# LitBit.net
KiCad netlist of a schematic drawn in EAGLE
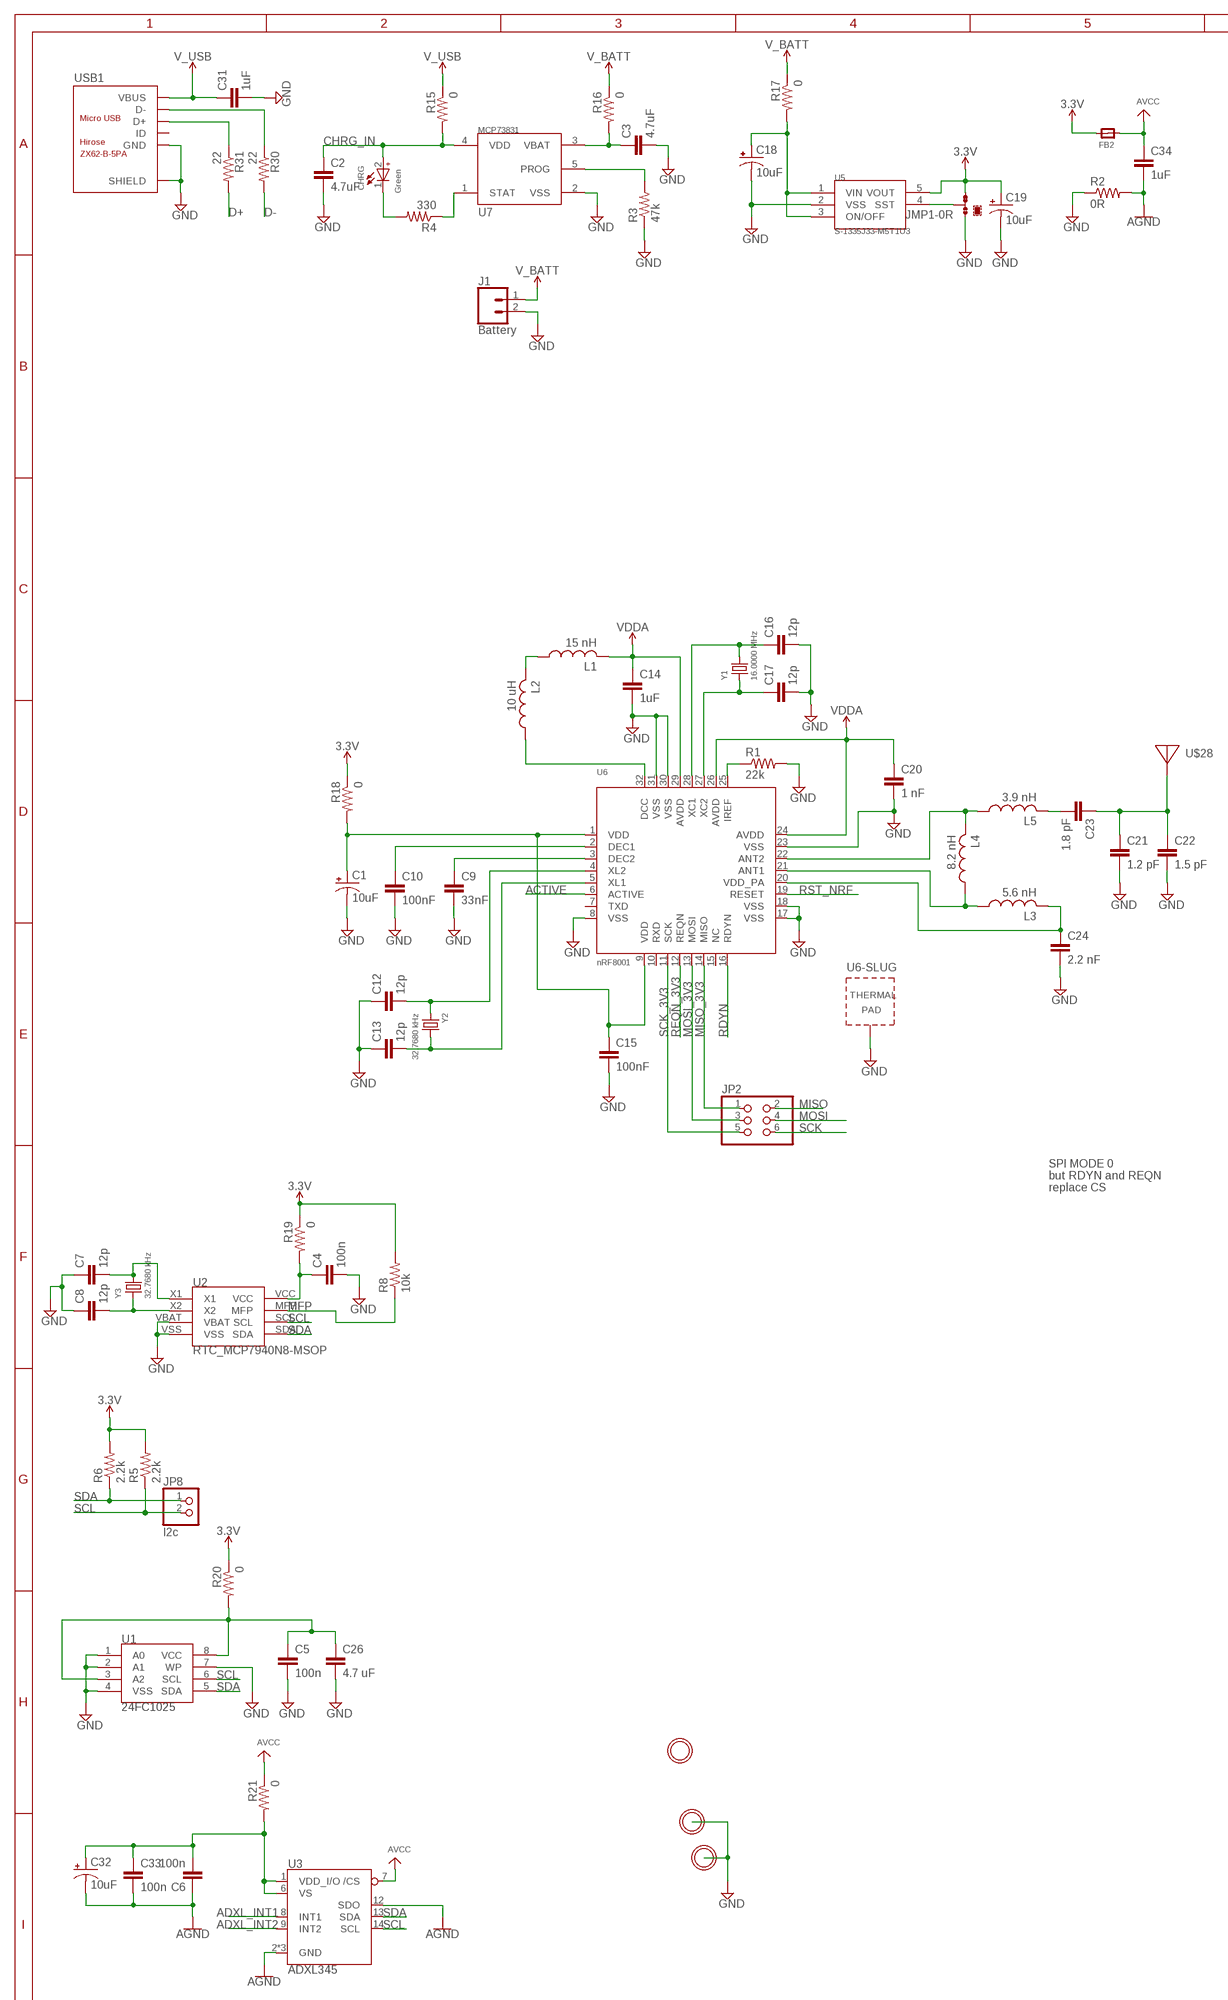
[diagram p0: schematic, sheet 1, part 1 of 2]
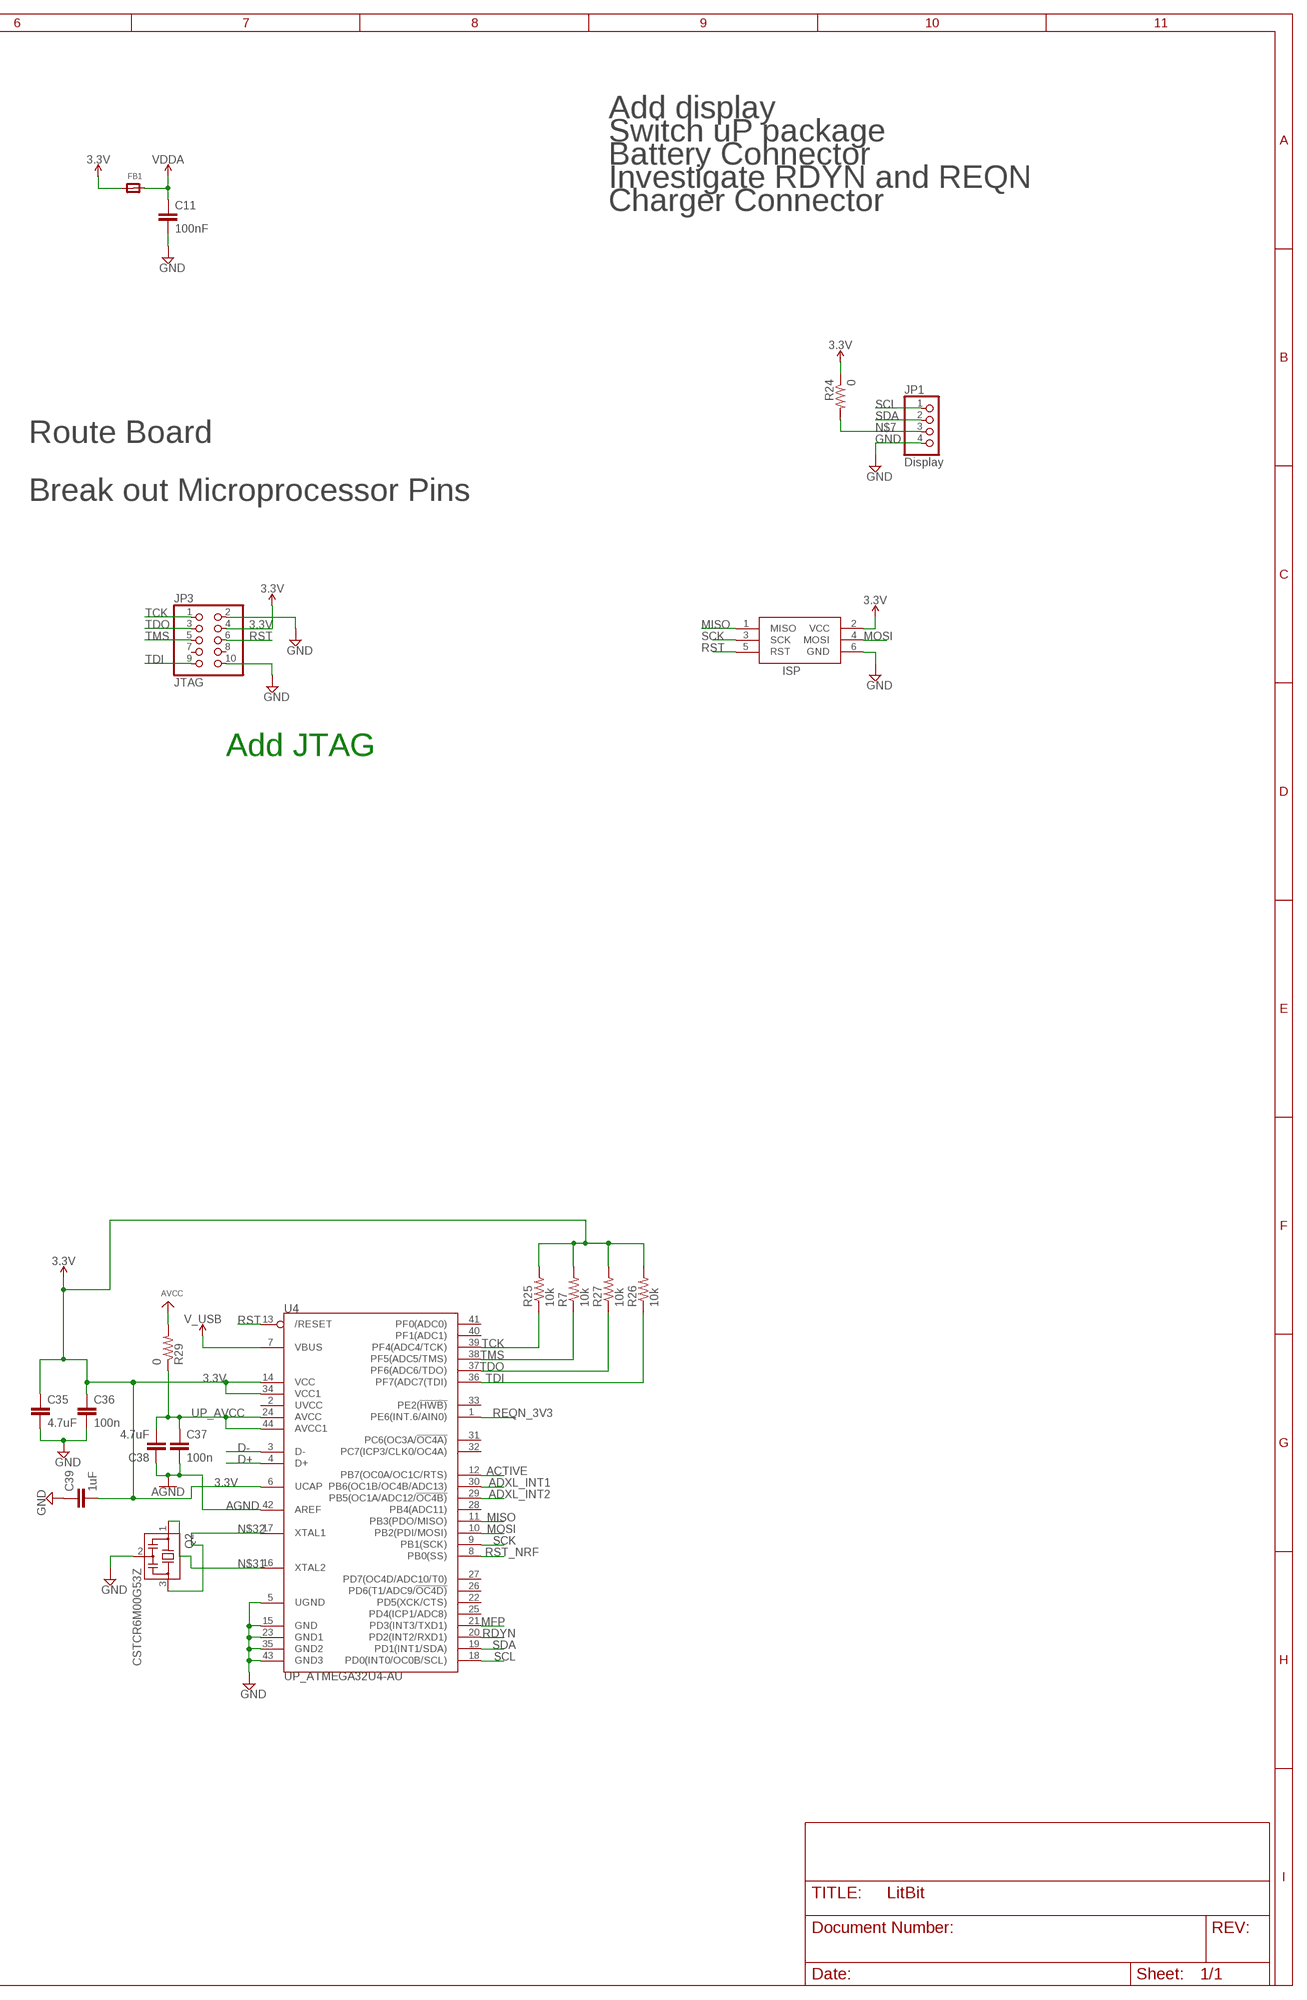
[diagram p1: schematic, sheet 1, part 2 of 2]

(export (version "E")
  (design (tool "Eeschema 10.0.6"))
  (components
    (comp (ref "C1")
      (value "10uF")
      (footprint "eagle-import:0603-POLAR")
      (libsource (lib "eagle-import") (part "CAP_POL_0603"))
    )
    (comp (ref "C2")
      (value "4.7uF")
      (footprint "eagle-import:0603-CUSTOM")
      (libsource (lib "eagle-import") (part "CAP_NONPOL_0603"))
    )
    (comp (ref "C3")
      (value "4.7uF")
      (footprint "eagle-import:0603-CUSTOM")
      (libsource (lib "eagle-import") (part "CAP_NONPOL_0603"))
    )
    (comp (ref "C4")
      (value "100n")
      (footprint "eagle-import:0603-CUSTOM")
      (libsource (lib "eagle-import") (part "CAP_NONPOL_0603"))
    )
    (comp (ref "C5")
      (value "100n")
      (footprint "eagle-import:0603-CUSTOM")
      (libsource (lib "eagle-import") (part "CAP_NONPOL_0603"))
    )
    (comp (ref "C6")
      (value "100n")
      (footprint "eagle-import:0603-CUSTOM")
      (libsource (lib "eagle-import") (part "CAP_NONPOL_0603"))
    )
    (comp (ref "C7")
      (value "12p")
      (footprint "eagle-import:0603-CUSTOM")
      (libsource (lib "eagle-import") (part "CAP_NONPOL_0603"))
    )
    (comp (ref "C8")
      (value "12p")
      (footprint "eagle-import:0603-CUSTOM")
      (libsource (lib "eagle-import") (part "CAP_NONPOL_0603"))
    )
    (comp (ref "C9")
      (value "33nF")
      (footprint "eagle-import:0603-CUSTOM")
      (libsource (lib "eagle-import") (part "CAP_NONPOL_0603"))
    )
    (comp (ref "C10")
      (value "100nF")
      (footprint "eagle-import:0603-CUSTOM")
      (libsource (lib "eagle-import") (part "CAP_NONPOL_0603"))
    )
    (comp (ref "C11")
      (value "100nF")
      (footprint "eagle-import:0603-CUSTOM")
      (libsource (lib "eagle-import") (part "CAP_NONPOL_0603"))
    )
    (comp (ref "C12")
      (value "12p")
      (footprint "eagle-import:0603-CUSTOM")
      (libsource (lib "eagle-import") (part "CAP_NONPOL_0603"))
    )
    (comp (ref "C13")
      (value "12p")
      (footprint "eagle-import:0603-CUSTOM")
      (libsource (lib "eagle-import") (part "CAP_NONPOL_0603"))
    )
    (comp (ref "C14")
      (value "1uF")
      (footprint "eagle-import:0603-CUSTOM")
      (libsource (lib "eagle-import") (part "CAP_NONPOL_0603"))
    )
    (comp (ref "C15")
      (value "100nF")
      (footprint "eagle-import:0603-CUSTOM")
      (libsource (lib "eagle-import") (part "CAP_NONPOL_0603"))
    )
    (comp (ref "C16")
      (value "12p")
      (footprint "eagle-import:0603-CUSTOM")
      (libsource (lib "eagle-import") (part "CAP_NONPOL_0603"))
    )
    (comp (ref "C17")
      (value "12p")
      (footprint "eagle-import:0603-CUSTOM")
      (libsource (lib "eagle-import") (part "CAP_NONPOL_0603"))
    )
    (comp (ref "C18")
      (value "10uF")
      (footprint "eagle-import:0603-POLAR")
      (libsource (lib "eagle-import") (part "CAP_POL_0603"))
    )
    (comp (ref "C19")
      (value "10uF")
      (footprint "eagle-import:0603-POLAR")
      (libsource (lib "eagle-import") (part "CAP_POL_0603"))
    )
    (comp (ref "C20")
      (value "1 nF")
      (footprint "eagle-import:0603-CUSTOM")
      (libsource (lib "eagle-import") (part "CAP_NONPOL_0603"))
    )
    (comp (ref "C21")
      (value "1.2 pF")
      (footprint "eagle-import:0603-CUSTOM")
      (libsource (lib "eagle-import") (part "CAP_NONPOL_0603"))
    )
    (comp (ref "C22")
      (value "1.5 pF")
      (footprint "eagle-import:0603-CUSTOM")
      (libsource (lib "eagle-import") (part "CAP_NONPOL_0603"))
    )
    (comp (ref "C23")
      (value "1.8 pF")
      (footprint "eagle-import:0603-CUSTOM")
      (libsource (lib "eagle-import") (part "CAP_NONPOL_0603"))
    )
    (comp (ref "C24")
      (value "2.2 nF")
      (footprint "eagle-import:0603-CUSTOM")
      (libsource (lib "eagle-import") (part "CAP_NONPOL_0603"))
    )
    (comp (ref "C26")
      (value "4.7 uF")
      (footprint "eagle-import:0603-CUSTOM")
      (libsource (lib "eagle-import") (part "CAP_NONPOL_0603"))
    )
    (comp (ref "C31")
      (value "1uF")
      (footprint "eagle-import:0603-CUSTOM")
      (libsource (lib "eagle-import") (part "CAP_NONPOL_0603"))
    )
    (comp (ref "C32")
      (value "10uF")
      (footprint "eagle-import:0603-POLAR")
      (libsource (lib "eagle-import") (part "CAP_POL_0603"))
    )
    (comp (ref "C33")
      (value "100n")
      (footprint "eagle-import:0603-CUSTOM")
      (libsource (lib "eagle-import") (part "CAP_NONPOL_0603"))
    )
    (comp (ref "C34")
      (value "1uF")
      (footprint "eagle-import:0603-CUSTOM")
      (libsource (lib "eagle-import") (part "CAP_NONPOL_0603"))
    )
    (comp (ref "C35")
      (value "4.7uF")
      (footprint "eagle-import:0603-CUSTOM")
      (libsource (lib "eagle-import") (part "CAP_NONPOL_0603"))
    )
    (comp (ref "C36")
      (value "100n")
      (footprint "eagle-import:0603-CUSTOM")
      (libsource (lib "eagle-import") (part "CAP_NONPOL_0603"))
    )
    (comp (ref "C37")
      (value "100n")
      (footprint "eagle-import:0603-CUSTOM")
      (libsource (lib "eagle-import") (part "CAP_NONPOL_0603"))
    )
    (comp (ref "C38")
      (value "4.7uF")
      (footprint "eagle-import:0603-CUSTOM")
      (libsource (lib "eagle-import") (part "CAP_NONPOL_0603"))
    )
    (comp (ref "C39")
      (value "1uF")
      (footprint "eagle-import:0603-CUSTOM")
      (libsource (lib "eagle-import") (part "CAP_NONPOL_0603"))
    )
    (comp (ref "CHRG")
      (value "Green")
      (footprint "eagle-import:0603-LED")
      (libsource (lib "eagle-import") (part "LED_WL-SMCW-150060GS75000"))
    )
    (comp (ref "FB1")
      (value "FERRITE")
      (footprint "eagle-import:0603-CUSTOM")
      (libsource (lib "eagle-import") (part "FERRITE"))
    )
    (comp (ref "FB2")
      (value "FERRITE")
      (footprint "eagle-import:0603-CUSTOM")
      (libsource (lib "eagle-import") (part "FERRITE"))
    )
    (comp (ref "GND")
      (value "MOUNTINGHOLE2.0")
      (footprint "eagle-import:MOUNTINGHOLE_2.0_PLATED")
      (libsource (lib "eagle-import") (part "MOUNTINGHOLE2.0"))
    )
    (comp (ref "ISP")
      (value "AVRISP-6")
      (footprint "eagle-import:AVRISP")
      (libsource (lib "eagle-import") (part "AVRISP-6"))
    )
    (comp (ref "J1")
      (value "Battery")
      (footprint "eagle-import:JST-2-SMD")
      (libsource (lib "eagle-import") (part "CONN_02-JST-2MM-SMT"))
    )
    (comp (ref "JMP1")
      (value "0R-JUMPA")
      (footprint "eagle-import:AOR-JMP-0603")
      (libsource (lib "eagle-import") (part "0R-JUMPA"))
    )
    (comp (ref "JP1")
      (value "Display")
      (footprint "eagle-import:1X04")
      (libsource (lib "eagle-import") (part "PINHD-1X4"))
    )
    (comp (ref "JP2")
      (value "PINHD-2X3")
      (footprint "eagle-import:2X03")
      (libsource (lib "eagle-import") (part "PINHD-2X3"))
    )
    (comp (ref "JP3")
      (value "JTAG")
      (footprint "eagle-import:2X05")
      (libsource (lib "eagle-import") (part "PINHD-2X5"))
    )
    (comp (ref "JP8")
      (value "I2c")
      (footprint "eagle-import:1X02")
      (libsource (lib "eagle-import") (part "PINHD-1X2"))
    )
    (comp (ref "L1")
      (value "15 nH")
      (footprint "eagle-import:0603-CUSTOM")
      (libsource (lib "eagle-import") (part "IND-0603"))
    )
    (comp (ref "L2")
      (value "10 uH")
      (footprint "eagle-import:0805-CUSTOM")
      (libsource (lib "eagle-import") (part "IND-0805"))
    )
    (comp (ref "L3")
      (value "5.6 nH")
      (footprint "eagle-import:0603-CUSTOM")
      (libsource (lib "eagle-import") (part "IND-0603"))
    )
    (comp (ref "L4")
      (value "8.2 nH")
      (footprint "eagle-import:0603-CUSTOM")
      (libsource (lib "eagle-import") (part "IND-0603"))
    )
    (comp (ref "L5")
      (value "3.9 nH")
      (footprint "eagle-import:0603-CUSTOM")
      (libsource (lib "eagle-import") (part "IND-0603"))
    )
    (comp (ref "Q2")
      (value "CSTCR6M00G53Z")
      (footprint "eagle-import:CSTCR6M")
      (fields (field (name "MPN") "CSTCR6M00G53-R0"))
      (libsource (lib "eagle-import") (part "CSTCR6M00G53Z"))
    )
    (comp (ref "R1")
      (value "22k")
      (footprint "eagle-import:0603-CUSTOM")
      (libsource (lib "eagle-import") (part "RES-0603"))
    )
    (comp (ref "R2")
      (value "0R")
      (footprint "eagle-import:0603-CUSTOM")
      (libsource (lib "eagle-import") (part "RES-0603"))
    )
    (comp (ref "R3")
      (value "47k")
      (footprint "eagle-import:0603-CUSTOM")
      (libsource (lib "eagle-import") (part "RES-0603"))
    )
    (comp (ref "R4")
      (value "330")
      (footprint "eagle-import:0603-CUSTOM")
      (libsource (lib "eagle-import") (part "RES-0603"))
    )
    (comp (ref "R5")
      (value "2.2k")
      (footprint "eagle-import:0603-CUSTOM")
      (libsource (lib "eagle-import") (part "RES-0603"))
    )
    (comp (ref "R6")
      (value "2.2k")
      (footprint "eagle-import:0603-CUSTOM")
      (libsource (lib "eagle-import") (part "RES-0603"))
    )
    (comp (ref "R7")
      (value "10k")
      (footprint "eagle-import:0603-CUSTOM")
      (libsource (lib "eagle-import") (part "RES-0603"))
    )
    (comp (ref "R8")
      (value "10k")
      (footprint "eagle-import:0603-CUSTOM")
      (libsource (lib "eagle-import") (part "RES-0603"))
    )
    (comp (ref "R15")
      (value "0")
      (footprint "eagle-import:0603-CUSTOM")
      (libsource (lib "eagle-import") (part "RES-0603"))
    )
    (comp (ref "R16")
      (value "0")
      (footprint "eagle-import:0603-CUSTOM")
      (libsource (lib "eagle-import") (part "RES-0603"))
    )
    (comp (ref "R17")
      (value "0")
      (footprint "eagle-import:0603-CUSTOM")
      (libsource (lib "eagle-import") (part "RES-0603"))
    )
    (comp (ref "R18")
      (value "0")
      (footprint "eagle-import:0603-CUSTOM")
      (libsource (lib "eagle-import") (part "RES-0603"))
    )
    (comp (ref "R19")
      (value "0")
      (footprint "eagle-import:0603-CUSTOM")
      (libsource (lib "eagle-import") (part "RES-0603"))
    )
    (comp (ref "R20")
      (value "0")
      (footprint "eagle-import:0603-CUSTOM")
      (libsource (lib "eagle-import") (part "RES-0603"))
    )
    (comp (ref "R21")
      (value "0")
      (footprint "eagle-import:0603-CUSTOM")
      (libsource (lib "eagle-import") (part "RES-0603"))
    )
    (comp (ref "R24")
      (value "0")
      (footprint "eagle-import:0603-CUSTOM")
      (libsource (lib "eagle-import") (part "RES-0603"))
    )
    (comp (ref "R25")
      (value "10k")
      (footprint "eagle-import:0603-CUSTOM")
      (libsource (lib "eagle-import") (part "RES-0603"))
    )
    (comp (ref "R26")
      (value "10k")
      (footprint "eagle-import:0603-CUSTOM")
      (libsource (lib "eagle-import") (part "RES-0603"))
    )
    (comp (ref "R27")
      (value "10k")
      (footprint "eagle-import:0603-CUSTOM")
      (libsource (lib "eagle-import") (part "RES-0603"))
    )
    (comp (ref "R29")
      (value "0")
      (footprint "eagle-import:0603-CUSTOM")
      (libsource (lib "eagle-import") (part "RES-0603"))
    )
    (comp (ref "R30")
      (value "22")
      (footprint "eagle-import:0603-CUSTOM")
      (libsource (lib "eagle-import") (part "RES-0603"))
    )
    (comp (ref "R31")
      (value "22")
      (footprint "eagle-import:0603-CUSTOM")
      (libsource (lib "eagle-import") (part "RES-0603"))
    )
    (comp (ref "U$8")
      (value "MOUNTINGHOLE2.0")
      (footprint "eagle-import:MOUNTINGHOLE_2.0_PLATED")
      (libsource (lib "eagle-import") (part "MOUNTINGHOLE2.0"))
    )
    (comp (ref "U$13")
      (value "MOUNTINGHOLE2.0")
      (footprint "eagle-import:MOUNTINGHOLE_2.0_PLATED")
      (libsource (lib "eagle-import") (part "MOUNTINGHOLE2.0"))
    )
    (comp (ref "U$28")
      (value "ANTENNA_PCBNRF8001_1.6MM")
      (footprint "eagle-import:ANT_PCB_2.4GHZ_NRF8001_1.6MM_1OZ")
      (libsource (lib "eagle-import") (part "ANTENNA_PCBNRF8001_1.6MM"))
    )
    (comp (ref "U1")
      (value "24FC1025")
      (footprint "eagle-import:8-SOIC_HAND_SOLDER")
      (libsource (lib "eagle-import") (part "24FC1025"))
    )
    (comp (ref "U2")
      (value "RTC_MCP7940N8-MSOP")
      (footprint "eagle-import:8-MSOP-CUSTOM")
      (libsource (lib "eagle-import") (part "RTC_MCP7940N8-MSOP"))
    )
    (comp (ref "U3")
      (value "ADXL345")
      (footprint "eagle-import:LGA-14")
      (libsource (lib "eagle-import") (part "ADXL345"))
    )
    (comp (ref "U4")
      (value "UP_ATMEGA32U4-AU")
      (footprint "eagle-import:TQFP44")
      (libsource (lib "eagle-import") (part "UP_ATMEGA32U4-AU"))
    )
    (comp (ref "U5")
      (value "S-1335J33-M5T1U3")
      (footprint "eagle-import:SOT23-5_HAND_SOLDER")
      (libsource (lib "eagle-import") (part "S-1335J33-M5T1U3"))
    )
    (comp (ref "U6")
      (value "nRF8001")
      (footprint "eagle-import:QFN32_5MM")
      (libsource (lib "eagle-import") (part "NRF8001"))
    )
    (comp (ref "U7")
      (value "MCP73831")
      (footprint "eagle-import:SOT23-5_HAND_SOLDER")
      (libsource (lib "eagle-import") (part "MCP73831"))
    )
    (comp (ref "USB1")
      (value "ZX62-B-5PA")
      (footprint "eagle-import:MICRO-USB5+6P-SMD-0.65-AB")
      (libsource (lib "eagle-import") (part "MICRO-USB-SMD(ZX62-B-5PA)"))
    )
    (comp (ref "Y1")
      (value "16.0000 MHz")
      (footprint "eagle-import:4-SMD")
      (libsource (lib "eagle-import") (part "FA-238_CRYSTAL"))
    )
    (comp (ref "Y2")
      (value "32.7680 kHz")
      (footprint "eagle-import:2-SMD")
      (libsource (lib "eagle-import") (part "CRYSTAL_ABS07"))
    )
    (comp (ref "Y3")
      (value "32.7680 kHz")
      (footprint "eagle-import:2-SMD")
      (libsource (lib "eagle-import") (part "CRYSTAL_ABS07"))
    )
  )
  (nets
    (net (code "1") (name "/ACTIVE") (class "Default")
      (node (ref "U4") (pin "12") (pinfunction "PB7(OC0A/OC1C/RTS)_12") (pintype "bidirectional"))
      (node (ref "U6") (pin "6") (pinfunction "ACTIVE_6") (pintype "output"))
    )
    (net (code "2") (name "/ADXL_INT1") (class "Default")
      (node (ref "U3") (pin "8") (pinfunction "INT1_8") (pintype "bidirectional"))
      (node (ref "U4") (pin "30") (pinfunction "PB6(OC1B/OC4B/ADC13)_30") (pintype "bidirectional"))
    )
    (net (code "3") (name "/ADXL_INT2") (class "Default")
      (node (ref "U3") (pin "9") (pinfunction "INT2_9") (pintype "bidirectional"))
      (node (ref "U4") (pin "29") (pinfunction "PB5(OC1A/ADC12/~{OC4B})_29") (pintype "bidirectional"))
    )
    (net (code "4") (name "/CHRG_IN") (class "Default")
      (node (ref "C2") (pin "1") (pinfunction "1_1") (pintype "passive"))
      (node (ref "CHRG") (pin "2") (pinfunction "+_2") (pintype "passive"))
      (node (ref "R15") (pin "2") (pinfunction "2_2") (pintype "passive"))
      (node (ref "U7") (pin "4") (pinfunction "VDD_4") (pintype "power_in"))
    )
    (net (code "5") (name "/D+") (class "Default")
      (node (ref "R31") (pin "2") (pinfunction "2_2") (pintype "passive"))
      (node (ref "U4") (pin "4") (pinfunction "D+_4") (pintype "bidirectional"))
    )
    (net (code "6") (name "/D-") (class "Default")
      (node (ref "R30") (pin "2") (pinfunction "2_2") (pintype "passive"))
      (node (ref "U4") (pin "3") (pinfunction "D-_3") (pintype "bidirectional"))
    )
    (net (code "7") (name "/MFP") (class "Default")
      (node (ref "R8") (pin "1") (pinfunction "1_1") (pintype "passive"))
      (node (ref "U2") (pin "MFP") (pinfunction "MFP_MFP") (pintype "output"))
      (node (ref "U4") (pin "21") (pinfunction "PD3(INT3/TXD1)_21") (pintype "bidirectional"))
    )
    (net (code "8") (name "/MISO") (class "Default")
      (node (ref "ISP") (pin "1") (pinfunction "MISO_1") (pintype "input"))
      (node (ref "JP2") (pin "2") (pinfunction "2_2") (pintype "passive"))
      (node (ref "U4") (pin "11") (pinfunction "PB3(PDO/MISO)_11") (pintype "bidirectional"))
    )
    (net (code "9") (name "/MISO_3V3") (class "Default")
      (node (ref "JP2") (pin "1") (pinfunction "1_1") (pintype "passive"))
      (node (ref "U6") (pin "14") (pinfunction "MISO_14") (pintype "output"))
    )
    (net (code "10") (name "/MOSI") (class "Default")
      (node (ref "ISP") (pin "4") (pinfunction "MOSI_4") (pintype "output"))
      (node (ref "JP2") (pin "4") (pinfunction "4_4") (pintype "passive"))
      (node (ref "U4") (pin "10") (pinfunction "PB2(PDI/MOSI)_10") (pintype "bidirectional"))
    )
    (net (code "11") (name "/MOSI_3V3") (class "Default")
      (node (ref "JP2") (pin "3") (pinfunction "3_3") (pintype "passive"))
      (node (ref "U6") (pin "13") (pinfunction "MOSI_13") (pintype "input"))
    )
    (net (code "12") (name "/N$7") (class "Default")
      (node (ref "JP1") (pin "3") (pinfunction "3_3") (pintype "passive"))
      (node (ref "R24") (pin "2") (pinfunction "2_2") (pintype "passive"))
    )
    (net (code "13") (name "/N$31") (class "Default")
      (node (ref "Q2") (pin "1") (pinfunction "1_1") (pintype "passive"))
      (node (ref "U4") (pin "16") (pinfunction "XTAL2_16") (pintype "bidirectional"))
    )
    (net (code "14") (name "/N$32") (class "Default")
      (node (ref "Q2") (pin "3") (pinfunction "3_3") (pintype "passive"))
      (node (ref "U4") (pin "17") (pinfunction "XTAL1_17") (pintype "bidirectional"))
    )
    (net (code "15") (name "/RDYN") (class "Default")
      (node (ref "U4") (pin "20") (pinfunction "PD2(INT2/RXD1)_20") (pintype "bidirectional"))
      (node (ref "U6") (pin "16") (pinfunction "RDYN_16") (pintype "output"))
    )
    (net (code "16") (name "/REQN_3V3") (class "Default")
      (node (ref "U4") (pin "1") (pinfunction "PE6(INT.6/AIN0)_1") (pintype "bidirectional"))
      (node (ref "U6") (pin "12") (pinfunction "REQN_12") (pintype "input"))
    )
    (net (code "17") (name "/RST") (class "Default")
      (node (ref "ISP") (pin "5") (pinfunction "RST_5") (pintype "output"))
      (node (ref "JP3") (pin "6") (pinfunction "6_6") (pintype "passive"))
      (node (ref "U4") (pin "13") (pinfunction "/RESET_13") (pintype "bidirectional"))
    )
    (net (code "18") (name "/RST_NRF") (class "Default")
      (node (ref "U4") (pin "8") (pinfunction "PB0(SS)_8") (pintype "bidirectional"))
      (node (ref "U6") (pin "19") (pinfunction "RESET_19") (pintype "input"))
    )
    (net (code "19") (name "/SCK") (class "Default")
      (node (ref "ISP") (pin "3") (pinfunction "SCK_3") (pintype "output"))
      (node (ref "JP2") (pin "6") (pinfunction "6_6") (pintype "passive"))
      (node (ref "U4") (pin "9") (pinfunction "PB1(SCK)_9") (pintype "bidirectional"))
    )
    (net (code "20") (name "/SCK_3V3") (class "Default")
      (node (ref "JP2") (pin "5") (pinfunction "5_5") (pintype "passive"))
      (node (ref "U6") (pin "11") (pinfunction "SCK_11") (pintype "input"))
    )
    (net (code "21") (name "/SCL") (class "Default")
      (node (ref "JP1") (pin "1") (pinfunction "1_1") (pintype "passive"))
      (node (ref "JP8") (pin "2") (pinfunction "2_2") (pintype "passive"))
      (node (ref "R5") (pin "1") (pinfunction "1_1") (pintype "passive"))
      (node (ref "U1") (pin "6") (pinfunction "SCL_6") (pintype "bidirectional"))
      (node (ref "U2") (pin "SCL") (pinfunction "SCL_SCL") (pintype "bidirectional"))
      (node (ref "U3") (pin "14") (pinfunction "SCL_14") (pintype "bidirectional"))
      (node (ref "U4") (pin "18") (pinfunction "PD0(INT0/OC0B/SCL)_18") (pintype "bidirectional"))
    )
    (net (code "22") (name "/SDA") (class "Default")
      (node (ref "JP1") (pin "2") (pinfunction "2_2") (pintype "passive"))
      (node (ref "JP8") (pin "1") (pinfunction "1_1") (pintype "passive"))
      (node (ref "R6") (pin "1") (pinfunction "1_1") (pintype "passive"))
      (node (ref "U1") (pin "5") (pinfunction "SDA_5") (pintype "bidirectional"))
      (node (ref "U2") (pin "SDA") (pinfunction "SDA_SDA") (pintype "bidirectional"))
      (node (ref "U3") (pin "13") (pinfunction "SDA_13") (pintype "bidirectional"))
      (node (ref "U4") (pin "19") (pinfunction "PD1(INT1/SDA)_19") (pintype "bidirectional"))
    )
    (net (code "23") (name "/TCK") (class "Default")
      (node (ref "JP3") (pin "1") (pinfunction "1_1") (pintype "passive"))
      (node (ref "R25") (pin "1") (pinfunction "1_1") (pintype "passive"))
      (node (ref "U4") (pin "39") (pinfunction "PF4(ADC4/TCK)_39") (pintype "bidirectional"))
    )
    (net (code "24") (name "/TDI") (class "Default")
      (node (ref "JP3") (pin "9") (pinfunction "9_9") (pintype "passive"))
      (node (ref "R26") (pin "1") (pinfunction "1_1") (pintype "passive"))
      (node (ref "U4") (pin "36") (pinfunction "PF7(ADC7(TDI)_36") (pintype "bidirectional"))
    )
    (net (code "25") (name "/TDO") (class "Default")
      (node (ref "JP3") (pin "3") (pinfunction "3_3") (pintype "passive"))
      (node (ref "R27") (pin "1") (pinfunction "1_1") (pintype "passive"))
      (node (ref "U4") (pin "37") (pinfunction "PF6(ADC6/TDO)_37") (pintype "bidirectional"))
    )
    (net (code "26") (name "/TMS") (class "Default")
      (node (ref "JP3") (pin "5") (pinfunction "5_5") (pintype "passive"))
      (node (ref "R7") (pin "1") (pinfunction "1_1") (pintype "passive"))
      (node (ref "U4") (pin "38") (pinfunction "PF5(ADC5/TMS)_38") (pintype "bidirectional"))
    )
    (net (code "27") (name "/UP_AVCC") (class "Default")
      (node (ref "C37") (pin "1") (pinfunction "1_1") (pintype "passive"))
      (node (ref "C38") (pin "2") (pinfunction "2_2") (pintype "passive"))
      (node (ref "R29") (pin "1") (pinfunction "1_1") (pintype "passive"))
      (node (ref "U4") (pin "24") (pinfunction "AVCC_24") (pintype "bidirectional"))
      (node (ref "U4") (pin "44") (pinfunction "AVCC1_44") (pintype "bidirectional"))
    )
    (net (code "28") (name "3.3V") (class "Default")
      (node (ref "C19") (pin "1") (pinfunction "+_1") (pintype "passive"))
      (node (ref "C35") (pin "1") (pinfunction "1_1") (pintype "passive"))
      (node (ref "C36") (pin "1") (pinfunction "1_1") (pintype "passive"))
      (node (ref "C39") (pin "2") (pinfunction "2_2") (pintype "passive"))
      (node (ref "FB1") (pin "1") (pinfunction "P$1_1") (pintype "passive"))
      (node (ref "FB2") (pin "2") (pinfunction "P$2_2") (pintype "passive"))
      (node (ref "ISP") (pin "2") (pinfunction "VCC_2") (pintype "power_in"))
      (node (ref "JMP1") (pin "3") (pinfunction "3_3") (pintype "passive"))
      (node (ref "JP3") (pin "4") (pinfunction "4_4") (pintype "passive"))
      (node (ref "R18") (pin "1") (pinfunction "1_1") (pintype "passive"))
      (node (ref "R19") (pin "1") (pinfunction "1_1") (pintype "passive"))
      (node (ref "R20") (pin "1") (pinfunction "1_1") (pintype "passive"))
      (node (ref "R24") (pin "1") (pinfunction "1_1") (pintype "passive"))
      (node (ref "R25") (pin "2") (pinfunction "2_2") (pintype "passive"))
      (node (ref "R26") (pin "2") (pinfunction "2_2") (pintype "passive"))
      (node (ref "R27") (pin "2") (pinfunction "2_2") (pintype "passive"))
      (node (ref "R5") (pin "2") (pinfunction "2_2") (pintype "passive"))
      (node (ref "R6") (pin "2") (pinfunction "2_2") (pintype "passive"))
      (node (ref "R7") (pin "2") (pinfunction "2_2") (pintype "passive"))
      (node (ref "R8") (pin "2") (pinfunction "2_2") (pintype "passive"))
      (node (ref "U4") (pin "14") (pinfunction "VCC_14") (pintype "bidirectional"))
      (node (ref "U4") (pin "34") (pinfunction "VCC1_34") (pintype "bidirectional"))
      (node (ref "U4") (pin "6") (pinfunction "UCAP_6") (pintype "bidirectional"))
      (node (ref "U5") (pin "5") (pinfunction "VOUT_5") (pintype "output"))
    )
    (net (code "29") (name "AGND") (class "Default")
      (node (ref "C32") (pin "2") (pinfunction "-_2") (pintype "passive"))
      (node (ref "C33") (pin "2") (pinfunction "2_2") (pintype "passive"))
      (node (ref "C34") (pin "2") (pinfunction "2_2") (pintype "passive"))
      (node (ref "C37") (pin "2") (pinfunction "2_2") (pintype "passive"))
      (node (ref "C38") (pin "1") (pinfunction "1_1") (pintype "passive"))
      (node (ref "C6") (pin "1") (pinfunction "1_1") (pintype "passive"))
      (node (ref "R2") (pin "2") (pinfunction "2_2") (pintype "passive"))
      (node (ref "U3") (pin "12") (pinfunction "SDO_12") (pintype "bidirectional"))
      (node (ref "U3") (pin "2") (pinfunction "GND_2") (pintype "bidirectional"))
      (node (ref "U3") (pin "4") (pinfunction "GND_4") (pintype "bidirectional"))
      (node (ref "U3") (pin "5") (pinfunction "GND_5") (pintype "bidirectional"))
      (node (ref "U4") (pin "42") (pinfunction "AREF_42") (pintype "bidirectional"))
    )
    (net (code "30") (name "AVCC") (class "Default")
      (node (ref "C34") (pin "1") (pinfunction "1_1") (pintype "passive"))
      (node (ref "FB2") (pin "1") (pinfunction "P$1_1") (pintype "passive"))
      (node (ref "R21") (pin "1") (pinfunction "1_1") (pintype "passive"))
      (node (ref "R29") (pin "2") (pinfunction "2_2") (pintype "passive"))
      (node (ref "U3") (pin "7") (pinfunction "/CS_7") (pintype "bidirectional"))
    )
    (net (code "31") (name "GND") (class "Default")
      (node (ref "C1") (pin "2") (pinfunction "-_2") (pintype "passive"))
      (node (ref "C10") (pin "2") (pinfunction "2_2") (pintype "passive"))
      (node (ref "C11") (pin "2") (pinfunction "2_2") (pintype "passive"))
      (node (ref "C12") (pin "1") (pinfunction "1_1") (pintype "passive"))
      (node (ref "C13") (pin "1") (pinfunction "1_1") (pintype "passive"))
      (node (ref "C14") (pin "2") (pinfunction "2_2") (pintype "passive"))
      (node (ref "C15") (pin "2") (pinfunction "2_2") (pintype "passive"))
      (node (ref "C16") (pin "2") (pinfunction "2_2") (pintype "passive"))
      (node (ref "C17") (pin "2") (pinfunction "2_2") (pintype "passive"))
      (node (ref "C18") (pin "2") (pinfunction "-_2") (pintype "passive"))
      (node (ref "C19") (pin "2") (pinfunction "-_2") (pintype "passive"))
      (node (ref "C2") (pin "2") (pinfunction "2_2") (pintype "passive"))
      (node (ref "C20") (pin "2") (pinfunction "2_2") (pintype "passive"))
      (node (ref "C21") (pin "2") (pinfunction "2_2") (pintype "passive"))
      (node (ref "C22") (pin "2") (pinfunction "2_2") (pintype "passive"))
      (node (ref "C24") (pin "2") (pinfunction "2_2") (pintype "passive"))
      (node (ref "C26") (pin "2") (pinfunction "2_2") (pintype "passive"))
      (node (ref "C3") (pin "2") (pinfunction "2_2") (pintype "passive"))
      (node (ref "C31") (pin "2") (pinfunction "2_2") (pintype "passive"))
      (node (ref "C35") (pin "2") (pinfunction "2_2") (pintype "passive"))
      (node (ref "C36") (pin "2") (pinfunction "2_2") (pintype "passive"))
      (node (ref "C39") (pin "1") (pinfunction "1_1") (pintype "passive"))
      (node (ref "C4") (pin "2") (pinfunction "2_2") (pintype "passive"))
      (node (ref "C5") (pin "2") (pinfunction "2_2") (pintype "passive"))
      (node (ref "C7") (pin "1") (pinfunction "1_1") (pintype "passive"))
      (node (ref "C8") (pin "1") (pinfunction "1_1") (pintype "passive"))
      (node (ref "C9") (pin "2") (pinfunction "2_2") (pintype "passive"))
      (node (ref "ISP") (pin "6") (pinfunction "GND_6") (pintype "power_in"))
      (node (ref "J1") (pin "2") (pinfunction "1_2") (pintype "passive"))
      (node (ref "JMP1") (pin "1") (pinfunction "1_1") (pintype "passive"))
      (node (ref "JP1") (pin "4") (pinfunction "4_4") (pintype "passive"))
      (node (ref "JP3") (pin "10") (pinfunction "10_10") (pintype "passive"))
      (node (ref "JP3") (pin "2") (pinfunction "2_2") (pintype "passive"))
      (node (ref "Q2") (pin "2") (pinfunction "2_2") (pintype "passive"))
      (node (ref "R1") (pin "2") (pinfunction "2_2") (pintype "passive"))
      (node (ref "R2") (pin "1") (pinfunction "1_1") (pintype "passive"))
      (node (ref "R3") (pin "1") (pinfunction "1_1") (pintype "passive"))
      (node (ref "U1") (pin "1") (pinfunction "A0_1") (pintype "input"))
      (node (ref "U1") (pin "2") (pinfunction "A1_2") (pintype "input"))
      (node (ref "U1") (pin "4") (pinfunction "VSS_4") (pintype "passive"))
      (node (ref "U1") (pin "7") (pinfunction "WP_7") (pintype "input"))
      (node (ref "U2") (pin "VBAT") (pinfunction "VBAT_VBAT") (pintype "input"))
      (node (ref "U2") (pin "VSS") (pinfunction "VSS_VSS") (pintype "passive"))
      (node (ref "U4") (pin "15") (pinfunction "GND_15") (pintype "bidirectional"))
      (node (ref "U4") (pin "23") (pinfunction "GND1_23") (pintype "bidirectional"))
      (node (ref "U4") (pin "35") (pinfunction "GND2_35") (pintype "bidirectional"))
      (node (ref "U4") (pin "43") (pinfunction "GND3_43") (pintype "bidirectional"))
      (node (ref "U4") (pin "5") (pinfunction "UGND_5") (pintype "bidirectional"))
      (node (ref "U5") (pin "2") (pinfunction "VSS_2") (pintype "passive"))
      (node (ref "U6") (pin "17") (pinfunction "VSS_17") (pintype "power_in"))
      (node (ref "U6") (pin "18") (pinfunction "VSS_18") (pintype "power_in"))
      (node (ref "U6") (pin "23") (pinfunction "VSS_23") (pintype "power_in"))
      (node (ref "U6") (pin "30") (pinfunction "VSS_30") (pintype "power_in"))
      (node (ref "U6") (pin "31") (pinfunction "VSS_31") (pintype "power_in"))
      (node (ref "U6") (pin "33") (pinfunction "TP_33") (pintype "power_in"))
      (node (ref "U6") (pin "8") (pinfunction "VSS_8") (pintype "power_in"))
      (node (ref "U7") (pin "2") (pinfunction "VSS_2") (pintype "power_in"))
      (node (ref "USB1") (pin "5") (pinfunction "GND_5") (pintype "power_in"))
      (node (ref "USB1") (pin "P1") (pinfunction "SHIELD_P1") (pintype "power_in"))
      (node (ref "USB1") (pin "P2") (pinfunction "SHIELD_P2") (pintype "power_in"))
      (node (ref "USB1") (pin "P3") (pinfunction "SHIELD_P3") (pintype "power_in"))
      (node (ref "USB1") (pin "P4") (pinfunction "SHIELD_P4") (pintype "power_in"))
      (node (ref "USB1") (pin "P5") (pinfunction "SHIELD_P5") (pintype "power_in"))
      (node (ref "USB1") (pin "P6") (pinfunction "SHIELD_P6") (pintype "power_in"))
    )
    (net (code "32") (name "Net-(C1-+)") (class "Default")
      (node (ref "C1") (pin "1") (pinfunction "+_1") (pintype "passive"))
      (node (ref "C15") (pin "1") (pinfunction "1_1") (pintype "passive"))
      (node (ref "R18") (pin "2") (pinfunction "2_2") (pintype "passive"))
      (node (ref "U6") (pin "1") (pinfunction "VDD_1") (pintype "power_in"))
      (node (ref "U6") (pin "9") (pinfunction "VDD_9") (pintype "power_in"))
    )
    (net (code "33") (name "Net-(C4-Pad1)") (class "Default")
      (node (ref "C4") (pin "1") (pinfunction "1_1") (pintype "passive"))
      (node (ref "R19") (pin "2") (pinfunction "2_2") (pintype "passive"))
      (node (ref "U2") (pin "VCC") (pinfunction "VCC_VCC") (pintype "passive"))
    )
    (net (code "34") (name "Net-(C18-+)") (class "Default")
      (node (ref "C18") (pin "1") (pinfunction "+_1") (pintype "passive"))
      (node (ref "R17") (pin "2") (pinfunction "2_2") (pintype "passive"))
      (node (ref "U5") (pin "1") (pinfunction "VIN_1") (pintype "input"))
      (node (ref "U5") (pin "3") (pinfunction "ON/OFF_3") (pintype "input"))
    )
    (net (code "35") (name "Net-(C23-Pad2)") (class "Default")
      (node (ref "C23") (pin "2") (pinfunction "2_2") (pintype "passive"))
      (node (ref "L5") (pin "2") (pinfunction "2_2") (pintype "passive"))
    )
    (net (code "36") (name "Net-(C32-+)") (class "Default")
      (node (ref "C32") (pin "1") (pinfunction "+_1") (pintype "passive"))
      (node (ref "C33") (pin "1") (pinfunction "1_1") (pintype "passive"))
      (node (ref "C6") (pin "2") (pinfunction "2_2") (pintype "passive"))
      (node (ref "R21") (pin "2") (pinfunction "2_2") (pintype "passive"))
      (node (ref "U3") (pin "1") (pinfunction "VDD_I/O_1") (pintype "bidirectional"))
      (node (ref "U3") (pin "6") (pinfunction "VS_6") (pintype "bidirectional"))
    )
    (net (code "37") (name "Net-(CHRG--)") (class "Default")
      (node (ref "CHRG") (pin "1") (pinfunction "-_1") (pintype "passive"))
      (node (ref "R4") (pin "2") (pinfunction "2_2") (pintype "passive"))
    )
    (net (code "38") (name "Net-(L1-Pad1)") (class "Default")
      (node (ref "L1") (pin "1") (pinfunction "1_1") (pintype "passive"))
      (node (ref "L2") (pin "2") (pinfunction "2_2") (pintype "passive"))
    )
    (net (code "39") (name "Net-(U$28-P$1)") (class "Default")
      (node (ref "C21") (pin "1") (pinfunction "1_1") (pintype "passive"))
      (node (ref "C22") (pin "1") (pinfunction "1_1") (pintype "passive"))
      (node (ref "C23") (pin "1") (pinfunction "1_1") (pintype "passive"))
      (node (ref "U$28") (pin "FEED") (pinfunction "P$1_FEED") (pintype "passive"))
    )
    (net (code "40") (name "Net-(U1-A2)") (class "Default")
      (node (ref "C26") (pin "1") (pinfunction "1_1") (pintype "passive"))
      (node (ref "C5") (pin "1") (pinfunction "1_1") (pintype "passive"))
      (node (ref "R20") (pin "2") (pinfunction "2_2") (pintype "passive"))
      (node (ref "U1") (pin "3") (pinfunction "A2_3") (pintype "input"))
      (node (ref "U1") (pin "8") (pinfunction "VCC_8") (pintype "passive"))
    )
    (net (code "41") (name "Net-(U5-SST)") (class "Default")
      (node (ref "JMP1") (pin "2") (pinfunction "2_2") (pintype "passive"))
      (node (ref "U5") (pin "4") (pinfunction "SST_4") (pintype "input"))
    )
    (net (code "42") (name "Net-(U6B-ANT1)") (class "Default")
      (node (ref "L3") (pin "1") (pinfunction "1_1") (pintype "passive"))
      (node (ref "L4") (pin "1") (pinfunction "1_1") (pintype "passive"))
      (node (ref "U6") (pin "21") (pinfunction "ANT1_21") (pintype "bidirectional"))
    )
    (net (code "43") (name "Net-(U6B-ANT2)") (class "Default")
      (node (ref "L4") (pin "2") (pinfunction "2_2") (pintype "passive"))
      (node (ref "L5") (pin "1") (pinfunction "1_1") (pintype "passive"))
      (node (ref "U6") (pin "22") (pinfunction "ANT2_22") (pintype "bidirectional"))
    )
    (net (code "44") (name "Net-(U6B-DCC)") (class "Default")
      (node (ref "L2") (pin "1") (pinfunction "1_1") (pintype "passive"))
      (node (ref "U6") (pin "32") (pinfunction "DCC_32") (pintype "bidirectional"))
    )
    (net (code "45") (name "Net-(U6B-DEC1)") (class "Default")
      (node (ref "C10") (pin "1") (pinfunction "1_1") (pintype "passive"))
      (node (ref "U6") (pin "2") (pinfunction "DEC1_2") (pintype "bidirectional"))
    )
    (net (code "46") (name "Net-(U6B-DEC2)") (class "Default")
      (node (ref "C9") (pin "1") (pinfunction "1_1") (pintype "passive"))
      (node (ref "U6") (pin "3") (pinfunction "DEC2_3") (pintype "bidirectional"))
    )
    (net (code "47") (name "Net-(U6B-IREF)") (class "Default")
      (node (ref "R1") (pin "1") (pinfunction "1_1") (pintype "passive"))
      (node (ref "U6") (pin "25") (pinfunction "IREF_25") (pintype "output"))
    )
    (net (code "48") (name "Net-(U6B-VDD_PA)") (class "Default")
      (node (ref "C24") (pin "1") (pinfunction "1_1") (pintype "passive"))
      (node (ref "L3") (pin "2") (pinfunction "2_2") (pintype "passive"))
      (node (ref "U6") (pin "20") (pinfunction "VDD_PA_20") (pintype "bidirectional"))
    )
    (net (code "49") (name "Net-(U6B-XC1)") (class "Default")
      (node (ref "C16") (pin "1") (pinfunction "1_1") (pintype "passive"))
      (node (ref "U6") (pin "28") (pinfunction "XC1_28") (pintype "input"))
      (node (ref "Y1") (pin "P3") (pinfunction "2_P3") (pintype "passive"))
    )
    (net (code "50") (name "Net-(U6B-XC2)") (class "Default")
      (node (ref "C17") (pin "1") (pinfunction "1_1") (pintype "passive"))
      (node (ref "U6") (pin "27") (pinfunction "XC2_27") (pintype "output"))
      (node (ref "Y1") (pin "P1") (pinfunction "1_P1") (pintype "passive"))
    )
    (net (code "51") (name "Net-(U6B-XL1)") (class "Default")
      (node (ref "C13") (pin "2") (pinfunction "2_2") (pintype "passive"))
      (node (ref "U6") (pin "5") (pinfunction "XL1_5") (pintype "input"))
      (node (ref "Y2") (pin "P$2") (pinfunction "2_P$2") (pintype "passive"))
    )
    (net (code "52") (name "Net-(U6B-XL2)") (class "Default")
      (node (ref "C12") (pin "2") (pinfunction "2_2") (pintype "passive"))
      (node (ref "U6") (pin "4") (pinfunction "XL2_4") (pintype "output"))
      (node (ref "Y2") (pin "P$1") (pinfunction "1_P$1") (pintype "passive"))
    )
    (net (code "53") (name "Net-(U7-PROG)") (class "Default")
      (node (ref "R3") (pin "2") (pinfunction "2_2") (pintype "passive"))
      (node (ref "U7") (pin "5") (pinfunction "PROG_5") (pintype "input"))
    )
    (net (code "54") (name "Net-(U7-STAT)") (class "Default")
      (node (ref "R4") (pin "1") (pinfunction "1_1") (pintype "passive"))
      (node (ref "U7") (pin "1") (pinfunction "STAT_1") (pintype "output"))
    )
    (net (code "55") (name "Net-(U7-VBAT)") (class "Default")
      (node (ref "C3") (pin "1") (pinfunction "1_1") (pintype "passive"))
      (node (ref "R16") (pin "2") (pinfunction "2_2") (pintype "passive"))
      (node (ref "U7") (pin "3") (pinfunction "VBAT_3") (pintype "bidirectional"))
    )
    (net (code "56") (name "Net-(USB1-D+)") (class "Default")
      (node (ref "R31") (pin "1") (pinfunction "1_1") (pintype "passive"))
      (node (ref "USB1") (pin "3") (pinfunction "D+_3") (pintype "bidirectional"))
    )
    (net (code "57") (name "Net-(USB1-D-)") (class "Default")
      (node (ref "R30") (pin "1") (pinfunction "1_1") (pintype "passive"))
      (node (ref "USB1") (pin "2") (pinfunction "D-_2") (pintype "bidirectional"))
    )
    (net (code "58") (name "Net-(Y3-1)") (class "Default")
      (node (ref "C8") (pin "2") (pinfunction "2_2") (pintype "passive"))
      (node (ref "U2") (pin "X2") (pinfunction "X2_X2") (pintype "passive"))
      (node (ref "Y3") (pin "P$1") (pinfunction "1_P$1") (pintype "passive"))
    )
    (net (code "59") (name "Net-(Y3-2)") (class "Default")
      (node (ref "C7") (pin "2") (pinfunction "2_2") (pintype "passive"))
      (node (ref "U2") (pin "X1") (pinfunction "X1_X1") (pintype "passive"))
      (node (ref "Y3") (pin "P$2") (pinfunction "2_P$2") (pintype "passive"))
    )
    (net (code "60") (name "VDDA") (class "Default")
      (node (ref "C11") (pin "1") (pinfunction "1_1") (pintype "passive"))
      (node (ref "C14") (pin "1") (pinfunction "1_1") (pintype "passive"))
      (node (ref "C20") (pin "1") (pinfunction "1_1") (pintype "passive"))
      (node (ref "FB1") (pin "2") (pinfunction "P$2_2") (pintype "passive"))
      (node (ref "L1") (pin "2") (pinfunction "2_2") (pintype "passive"))
      (node (ref "U6") (pin "24") (pinfunction "AVDD_24") (pintype "power_in"))
      (node (ref "U6") (pin "26") (pinfunction "AVDD_26") (pintype "power_in"))
      (node (ref "U6") (pin "29") (pinfunction "AVDD_29") (pintype "power_in"))
    )
    (net (code "61") (name "V_BATT") (class "Default")
      (node (ref "J1") (pin "1") (pinfunction "2_1") (pintype "passive"))
      (node (ref "R16") (pin "1") (pinfunction "1_1") (pintype "passive"))
      (node (ref "R17") (pin "1") (pinfunction "1_1") (pintype "passive"))
    )
    (net (code "62") (name "V_USB") (class "Default")
      (node (ref "C31") (pin "1") (pinfunction "1_1") (pintype "passive"))
      (node (ref "R15") (pin "1") (pinfunction "1_1") (pintype "passive"))
      (node (ref "U4") (pin "7") (pinfunction "VBUS_7") (pintype "bidirectional"))
      (node (ref "USB1") (pin "1") (pinfunction "VBUS_1") (pintype "power_in"))
    )
    (net (code "63") (name "unconnected-(JP3-Pad7)") (class "Default")
      (node (ref "JP3") (pin "7") (pinfunction "7_7") (pintype "passive"))
    )
    (net (code "64") (name "unconnected-(JP3-Pad8)") (class "Default")
      (node (ref "JP3") (pin "8") (pinfunction "8_8") (pintype "passive"))
    )
    (net (code "65") (name "unconnected-(U4-PB4(ADC11)-Pad28)") (class "Default")
      (node (ref "U4") (pin "28") (pinfunction "PB4(ADC11)_28") (pintype "bidirectional"))
    )
    (net (code "66") (name "unconnected-(U4-PC6(OC3A{slash}~{OC4A})-Pad31)") (class "Default")
      (node (ref "U4") (pin "31") (pinfunction "PC6(OC3A/~{OC4A})_31") (pintype "bidirectional"))
    )
    (net (code "67") (name "unconnected-(U4-PC7(ICP3{slash}CLK0{slash}OC4A)-Pad32)") (class "Default")
      (node (ref "U4") (pin "32") (pinfunction "PC7(ICP3/CLK0/OC4A)_32") (pintype "bidirectional"))
    )
    (net (code "68") (name "unconnected-(U4-PD4(ICP1{slash}ADC8)-Pad25)") (class "Default")
      (node (ref "U4") (pin "25") (pinfunction "PD4(ICP1/ADC8)_25") (pintype "bidirectional"))
    )
    (net (code "69") (name "unconnected-(U4-PD5(XCK{slash}CTS)-Pad22)") (class "Default")
      (node (ref "U4") (pin "22") (pinfunction "PD5(XCK/CTS)_22") (pintype "bidirectional"))
    )
    (net (code "70") (name "unconnected-(U4-PD6(T1{slash}ADC9{slash}~{OC4D})-Pad26)") (class "Default")
      (node (ref "U4") (pin "26") (pinfunction "PD6(T1/ADC9/~{OC4D})_26") (pintype "bidirectional"))
    )
    (net (code "71") (name "unconnected-(U4-PD7(OC4D{slash}ADC10{slash}T0)-Pad27)") (class "Default")
      (node (ref "U4") (pin "27") (pinfunction "PD7(OC4D/ADC10/T0)_27") (pintype "bidirectional"))
    )
    (net (code "72") (name "unconnected-(U4-PE2(~{HWB})-Pad33)") (class "Default")
      (node (ref "U4") (pin "33") (pinfunction "PE2(~{HWB})_33") (pintype "bidirectional"))
    )
    (net (code "73") (name "unconnected-(U4-PF0(ADC0)-Pad41)") (class "Default")
      (node (ref "U4") (pin "41") (pinfunction "PF0(ADC0)_41") (pintype "bidirectional"))
    )
    (net (code "74") (name "unconnected-(U4-PF1(ADC1)-Pad40)") (class "Default")
      (node (ref "U4") (pin "40") (pinfunction "PF1(ADC1)_40") (pintype "bidirectional"))
    )
    (net (code "75") (name "unconnected-(U4-UVCC-Pad2)") (class "Default")
      (node (ref "U4") (pin "2") (pinfunction "UVCC_2") (pintype "bidirectional"))
    )
    (net (code "76") (name "unconnected-(U6B-NC-Pad15)") (class "Default")
      (node (ref "U6") (pin "15") (pinfunction "NC_15") (pintype "no_connect"))
    )
    (net (code "77") (name "unconnected-(U6B-RXD-Pad10)") (class "Default")
      (node (ref "U6") (pin "10") (pinfunction "RXD_10") (pintype "input"))
    )
    (net (code "78") (name "unconnected-(U6B-TXD-Pad7)") (class "Default")
      (node (ref "U6") (pin "7") (pinfunction "TXD_7") (pintype "output"))
    )
    (net (code "79") (name "unconnected-(USB1-ID-Pad4)") (class "Default")
      (node (ref "USB1") (pin "4") (pinfunction "ID_4") (pintype "bidirectional"))
    )
  )
)
